# 08D-005.net
KiCad netlist of a schematic drawn in EAGLE
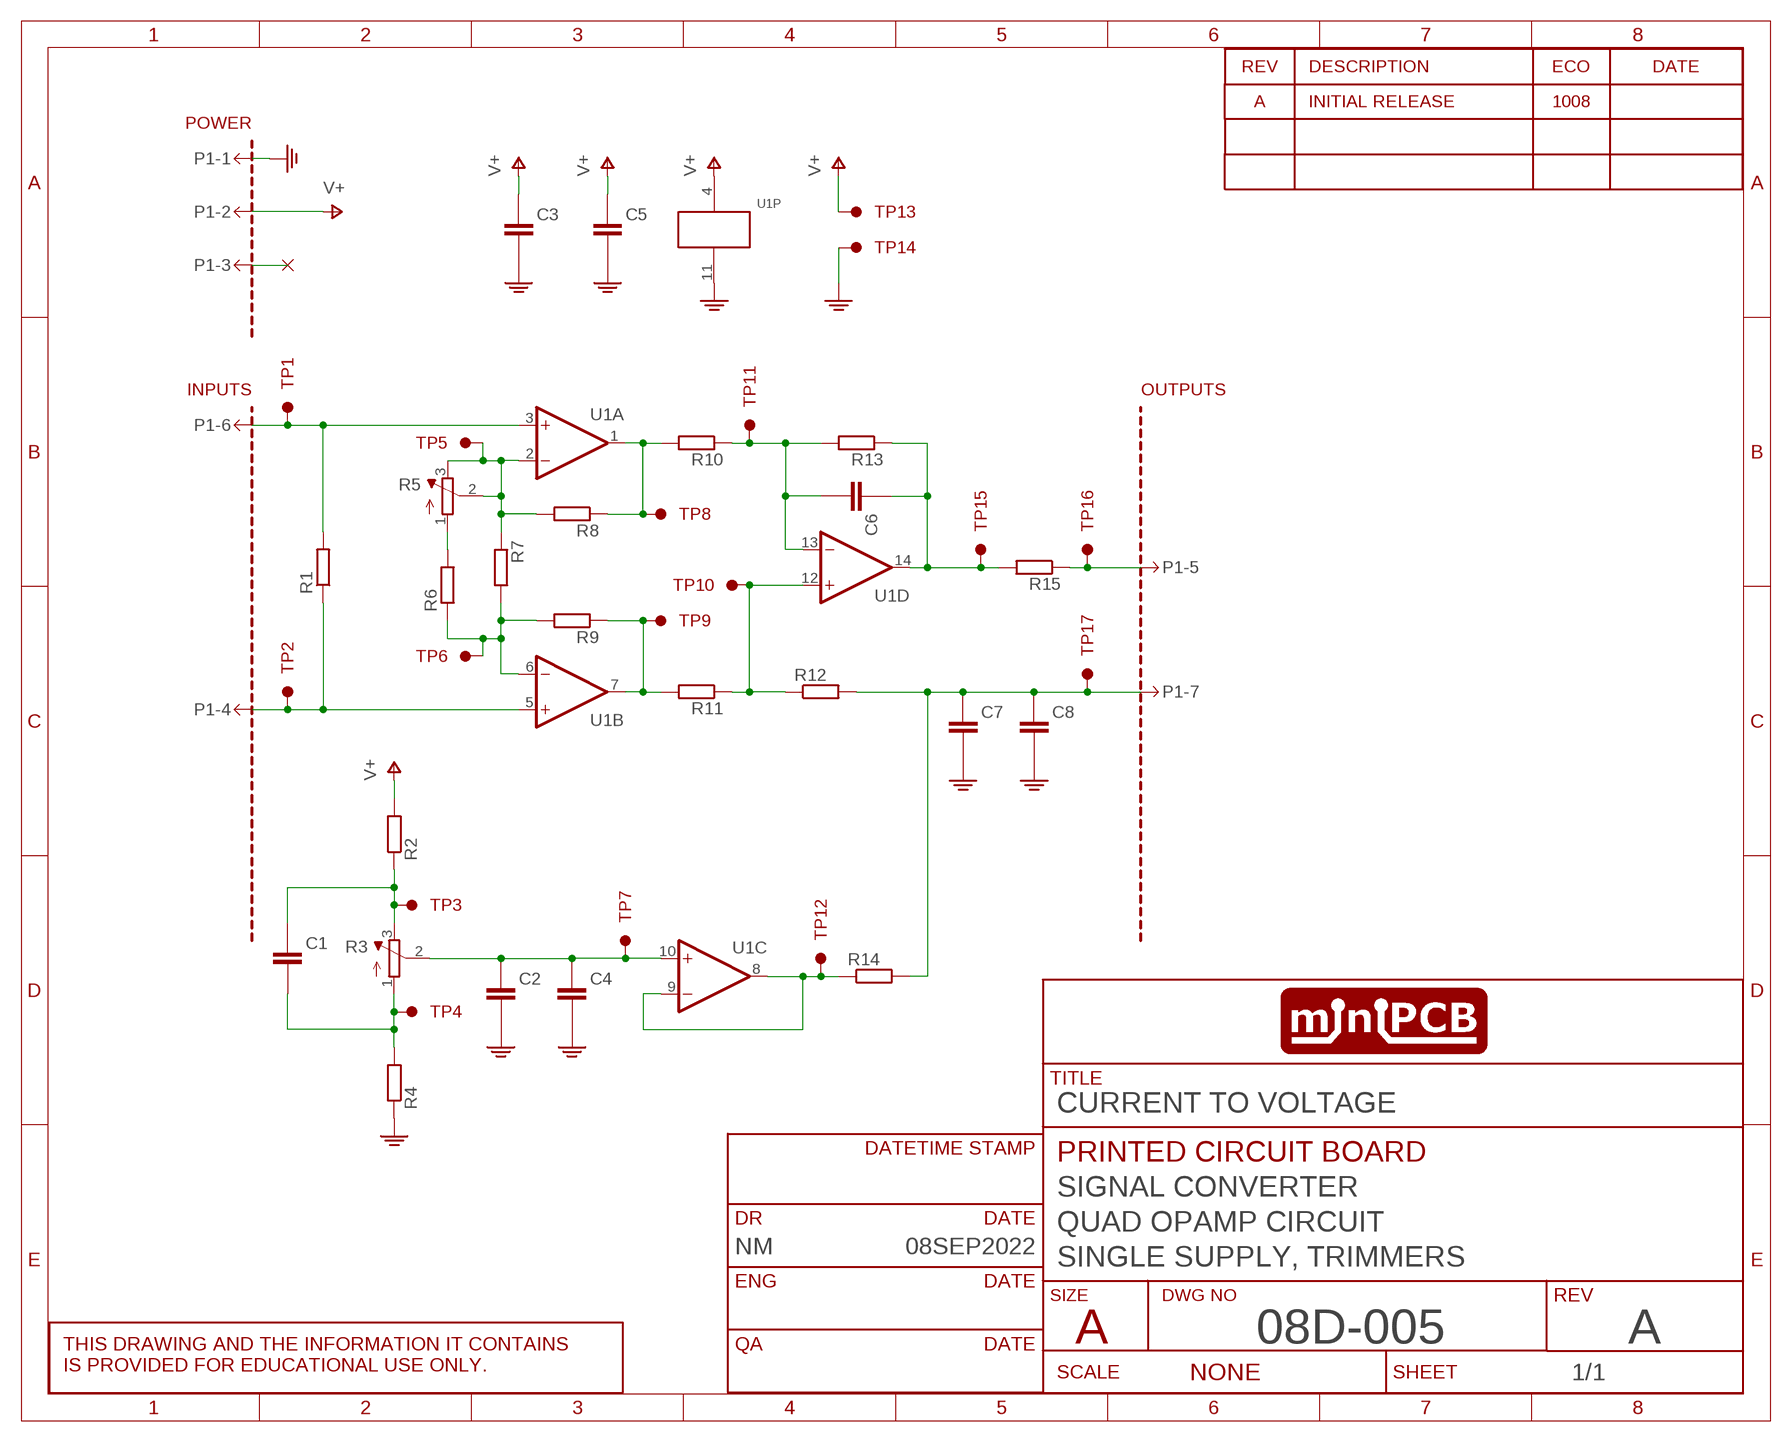
[diagram p0: schematic, sheet 1]

(export (version "E")
  (design (tool "Eeschema 10.0.6"))
  (components
    (comp (ref "C1")
      (value "CAPACITORTHD")
      (footprint "eagle-import:C050-024X044")
      (libsource (lib "eagle-import") (part "CAPACITORTHD"))
    )
    (comp (ref "C2")
      (value "CAPACITORTHD")
      (footprint "eagle-import:C050-024X044")
      (libsource (lib "eagle-import") (part "CAPACITORTHD"))
    )
    (comp (ref "C3")
      (value "CAPACITORTHD")
      (footprint "eagle-import:C050-024X044")
      (libsource (lib "eagle-import") (part "CAPACITORTHD"))
    )
    (comp (ref "C4")
      (value "CAPACITORTHD")
      (footprint "eagle-import:C050-024X044")
      (libsource (lib "eagle-import") (part "CAPACITORTHD"))
    )
    (comp (ref "C5")
      (value "CAPACITORTHD")
      (footprint "eagle-import:C050-024X044")
      (libsource (lib "eagle-import") (part "CAPACITORTHD"))
    )
    (comp (ref "C6")
      (value "CAPACITORTHD")
      (footprint "eagle-import:C050-024X044")
      (libsource (lib "eagle-import") (part "CAPACITORTHD"))
    )
    (comp (ref "C7")
      (value "CAPACITORTHD")
      (footprint "eagle-import:C050-024X044")
      (libsource (lib "eagle-import") (part "CAPACITORTHD"))
    )
    (comp (ref "C8")
      (value "CAPACITORTHD")
      (footprint "eagle-import:C050-024X044")
      (libsource (lib "eagle-import") (part "CAPACITORTHD"))
    )
    (comp (ref "P1-")
      (value "MINIPCB_7P50X100")
      (footprint "eagle-import:MINIPCB_7P_50X100")
      (fields (field (name "PART_NUMBER") "X08D-005-A"))
      (libsource (lib "eagle-import") (part "MINIPCB_7P50X100"))
    )
    (comp (ref "R1")
      (value "RESISTOR10MM")
      (footprint "eagle-import:0207_10")
      (libsource (lib "eagle-import") (part "RESISTOR10MM"))
    )
    (comp (ref "R2")
      (value "RESISTOR10MM")
      (footprint "eagle-import:0207_10")
      (libsource (lib "eagle-import") (part "RESISTOR10MM"))
    )
    (comp (ref "R3")
      (value "TRIMPOT0.100THD")
      (footprint "eagle-import:TRIM_0100")
      (libsource (lib "eagle-import") (part "TRIMPOT0.100THD"))
    )
    (comp (ref "R4")
      (value "RESISTOR10MM")
      (footprint "eagle-import:0207_10")
      (libsource (lib "eagle-import") (part "RESISTOR10MM"))
    )
    (comp (ref "R5")
      (value "TRIMPOT0.100THD")
      (footprint "eagle-import:TRIM_0100")
      (libsource (lib "eagle-import") (part "TRIMPOT0.100THD"))
    )
    (comp (ref "R6")
      (value "RESISTOR10MM")
      (footprint "eagle-import:0207_10")
      (libsource (lib "eagle-import") (part "RESISTOR10MM"))
    )
    (comp (ref "R7")
      (value "RESISTOR10MM")
      (footprint "eagle-import:0207_10")
      (libsource (lib "eagle-import") (part "RESISTOR10MM"))
    )
    (comp (ref "R8")
      (value "RESISTOR10MM")
      (footprint "eagle-import:0207_10")
      (libsource (lib "eagle-import") (part "RESISTOR10MM"))
    )
    (comp (ref "R9")
      (value "RESISTOR10MM")
      (footprint "eagle-import:0207_10")
      (libsource (lib "eagle-import") (part "RESISTOR10MM"))
    )
    (comp (ref "R10")
      (value "RESISTOR10MM")
      (footprint "eagle-import:0207_10")
      (libsource (lib "eagle-import") (part "RESISTOR10MM"))
    )
    (comp (ref "R11")
      (value "RESISTOR10MM")
      (footprint "eagle-import:0207_10")
      (libsource (lib "eagle-import") (part "RESISTOR10MM"))
    )
    (comp (ref "R12")
      (value "RESISTOR10MM")
      (footprint "eagle-import:0207_10")
      (libsource (lib "eagle-import") (part "RESISTOR10MM"))
    )
    (comp (ref "R13")
      (value "RESISTOR10MM")
      (footprint "eagle-import:0207_10")
      (libsource (lib "eagle-import") (part "RESISTOR10MM"))
    )
    (comp (ref "R14")
      (value "RESISTOR10MM")
      (footprint "eagle-import:0207_10")
      (libsource (lib "eagle-import") (part "RESISTOR10MM"))
    )
    (comp (ref "R15")
      (value "RESISTOR10MM")
      (footprint "eagle-import:0207_10")
      (libsource (lib "eagle-import") (part "RESISTOR10MM"))
    )
    (comp (ref "TP1")
      (value "TESTPOINTKE5000-SMTEXT")
      (footprint "eagle-import:PINS_1_TESTPOINT_KE5000_NOTEXT")
      (libsource (lib "eagle-import") (part "TESTPOINTKE5000-SMTEXT"))
    )
    (comp (ref "TP2")
      (value "TESTPOINTKE5000-SMTEXT")
      (footprint "eagle-import:PINS_1_TESTPOINT_KE5000_NOTEXT")
      (libsource (lib "eagle-import") (part "TESTPOINTKE5000-SMTEXT"))
    )
    (comp (ref "TP3")
      (value "TESTPOINTKE5000-SMTEXT")
      (footprint "eagle-import:PINS_1_TESTPOINT_KE5000_NOTEXT")
      (libsource (lib "eagle-import") (part "TESTPOINTKE5000-SMTEXT"))
    )
    (comp (ref "TP4")
      (value "TESTPOINTKE5000-SMTEXT")
      (footprint "eagle-import:PINS_1_TESTPOINT_KE5000_NOTEXT")
      (libsource (lib "eagle-import") (part "TESTPOINTKE5000-SMTEXT"))
    )
    (comp (ref "TP5")
      (value "TESTPOINTKE5000-SMTEXT")
      (footprint "eagle-import:PINS_1_TESTPOINT_KE5000_NOTEXT")
      (libsource (lib "eagle-import") (part "TESTPOINTKE5000-SMTEXT"))
    )
    (comp (ref "TP6")
      (value "TESTPOINTKE5000-SMTEXT")
      (footprint "eagle-import:PINS_1_TESTPOINT_KE5000_NOTEXT")
      (libsource (lib "eagle-import") (part "TESTPOINTKE5000-SMTEXT"))
    )
    (comp (ref "TP7")
      (value "TESTPOINTKE5000-SMTEXT")
      (footprint "eagle-import:PINS_1_TESTPOINT_KE5000_NOTEXT")
      (libsource (lib "eagle-import") (part "TESTPOINTKE5000-SMTEXT"))
    )
    (comp (ref "TP8")
      (value "TESTPOINTKE5000-SMTEXT")
      (footprint "eagle-import:PINS_1_TESTPOINT_KE5000_NOTEXT")
      (libsource (lib "eagle-import") (part "TESTPOINTKE5000-SMTEXT"))
    )
    (comp (ref "TP9")
      (value "TESTPOINTKE5000-SMTEXT")
      (footprint "eagle-import:PINS_1_TESTPOINT_KE5000_NOTEXT")
      (libsource (lib "eagle-import") (part "TESTPOINTKE5000-SMTEXT"))
    )
    (comp (ref "TP10")
      (value "TESTPOINTKE5000-SMTEXT")
      (footprint "eagle-import:PINS_1_TESTPOINT_KE5000_NOTEXT")
      (libsource (lib "eagle-import") (part "TESTPOINTKE5000-SMTEXT"))
    )
    (comp (ref "TP11")
      (value "TESTPOINTKE5000-SMTEXT")
      (footprint "eagle-import:PINS_1_TESTPOINT_KE5000_NOTEXT")
      (libsource (lib "eagle-import") (part "TESTPOINTKE5000-SMTEXT"))
    )
    (comp (ref "TP12")
      (value "TESTPOINTKE5000-SMTEXT")
      (footprint "eagle-import:PINS_1_TESTPOINT_KE5000_NOTEXT")
      (libsource (lib "eagle-import") (part "TESTPOINTKE5000-SMTEXT"))
    )
    (comp (ref "TP13")
      (value "TESTPOINTKE5000-SMTEXT")
      (footprint "eagle-import:PINS_1_TESTPOINT_KE5000_NOTEXT")
      (libsource (lib "eagle-import") (part "TESTPOINTKE5000-SMTEXT"))
    )
    (comp (ref "TP14")
      (value "TESTPOINTKE5000-SMTEXT")
      (footprint "eagle-import:PINS_1_TESTPOINT_KE5000_NOTEXT")
      (libsource (lib "eagle-import") (part "TESTPOINTKE5000-SMTEXT"))
    )
    (comp (ref "TP15")
      (value "TESTPOINTKE5000-SMTEXT")
      (footprint "eagle-import:PINS_1_TESTPOINT_KE5000_NOTEXT")
      (libsource (lib "eagle-import") (part "TESTPOINTKE5000-SMTEXT"))
    )
    (comp (ref "TP16")
      (value "TESTPOINTKE5000-SMTEXT")
      (footprint "eagle-import:PINS_1_TESTPOINT_KE5000_NOTEXT")
      (libsource (lib "eagle-import") (part "TESTPOINTKE5000-SMTEXT"))
    )
    (comp (ref "TP17")
      (value "TESTPOINTKE5000-SMTEXT")
      (footprint "eagle-import:PINS_1_TESTPOINT_KE5000_NOTEXT")
      (libsource (lib "eagle-import") (part "TESTPOINTKE5000-SMTEXT"))
    )
    (comp (ref "U1")
      (value "OPAMP_QUADTHD")
      (footprint "eagle-import:DIL14")
      (libsource (lib "eagle-import") (part "OPAMP_QUADTHD"))
    )
  )
  (nets
    (net (code "1") (name "GND") (class "Default")
      (node (ref "C2") (pin "2") (pinfunction "-_2") (pintype "passive"))
      (node (ref "C3") (pin "2") (pinfunction "-_2") (pintype "passive"))
      (node (ref "C4") (pin "2") (pinfunction "-_2") (pintype "passive"))
      (node (ref "C5") (pin "2") (pinfunction "-_2") (pintype "passive"))
      (node (ref "C7") (pin "2") (pinfunction "-_2") (pintype "passive"))
      (node (ref "C8") (pin "2") (pinfunction "-_2") (pintype "passive"))
      (node (ref "P1-") (pin "1") (pinfunction "1_1") (pintype "bidirectional"))
      (node (ref "R4") (pin "1") (pinfunction "1_1") (pintype "passive"))
      (node (ref "TP14") (pin "1") (pinfunction "1_1") (pintype "bidirectional"))
      (node (ref "U1") (pin "11") (pinfunction "V-_11") (pintype "power_in"))
    )
    (net (code "2") (name "Net-(C1-+)") (class "Default")
      (node (ref "C1") (pin "1") (pinfunction "+_1") (pintype "passive"))
      (node (ref "R2") (pin "1") (pinfunction "1_1") (pintype "passive"))
      (node (ref "R3") (pin "3") (pinfunction "E_3") (pintype "passive"))
      (node (ref "TP3") (pin "1") (pinfunction "1_1") (pintype "bidirectional"))
    )
    (net (code "3") (name "Net-(C1--)") (class "Default")
      (node (ref "C1") (pin "2") (pinfunction "-_2") (pintype "passive"))
      (node (ref "R3") (pin "1") (pinfunction "A_1") (pintype "passive"))
      (node (ref "R4") (pin "2") (pinfunction "2_2") (pintype "passive"))
      (node (ref "TP4") (pin "1") (pinfunction "1_1") (pintype "bidirectional"))
    )
    (net (code "4") (name "Net-(C2-+)") (class "Default")
      (node (ref "C2") (pin "1") (pinfunction "+_1") (pintype "passive"))
      (node (ref "C4") (pin "1") (pinfunction "+_1") (pintype "passive"))
      (node (ref "R3") (pin "2") (pinfunction "S_2") (pintype "passive"))
      (node (ref "TP7") (pin "1") (pinfunction "1_1") (pintype "bidirectional"))
      (node (ref "U1") (pin "10") (pinfunction "+IN_10") (pintype "input"))
    )
    (net (code "5") (name "Net-(C6-+)") (class "Default")
      (node (ref "C6") (pin "1") (pinfunction "+_1") (pintype "passive"))
      (node (ref "R13") (pin "1") (pinfunction "1_1") (pintype "passive"))
      (node (ref "R15") (pin "2") (pinfunction "2_2") (pintype "passive"))
      (node (ref "TP15") (pin "1") (pinfunction "1_1") (pintype "bidirectional"))
      (node (ref "U1") (pin "14") (pinfunction "OUT_14") (pintype "output"))
    )
    (net (code "6") (name "Net-(C6--)") (class "Default")
      (node (ref "C6") (pin "2") (pinfunction "-_2") (pintype "passive"))
      (node (ref "R10") (pin "1") (pinfunction "1_1") (pintype "passive"))
      (node (ref "R13") (pin "2") (pinfunction "2_2") (pintype "passive"))
      (node (ref "TP11") (pin "1") (pinfunction "1_1") (pintype "bidirectional"))
      (node (ref "U1") (pin "13") (pinfunction "-IN_13") (pintype "input"))
    )
    (net (code "7") (name "Net-(C7-+)") (class "Default")
      (node (ref "C7") (pin "1") (pinfunction "+_1") (pintype "passive"))
      (node (ref "C8") (pin "1") (pinfunction "+_1") (pintype "passive"))
      (node (ref "P1-") (pin "7") (pinfunction "1_7") (pintype "bidirectional"))
      (node (ref "R12") (pin "2") (pinfunction "2_2") (pintype "passive"))
      (node (ref "R14") (pin "2") (pinfunction "2_2") (pintype "passive"))
      (node (ref "TP17") (pin "1") (pinfunction "1_1") (pintype "bidirectional"))
    )
    (net (code "8") (name "Net-(P1-D-1)") (class "Default")
      (node (ref "P1-") (pin "4") (pinfunction "1_4") (pintype "bidirectional"))
      (node (ref "R1") (pin "1") (pinfunction "1_1") (pintype "passive"))
      (node (ref "TP2") (pin "1") (pinfunction "1_1") (pintype "bidirectional"))
      (node (ref "U1") (pin "5") (pinfunction "+IN_5") (pintype "input"))
    )
    (net (code "9") (name "Net-(P1-E-1)") (class "Default")
      (node (ref "P1-") (pin "5") (pinfunction "1_5") (pintype "bidirectional"))
      (node (ref "R15") (pin "1") (pinfunction "1_1") (pintype "passive"))
      (node (ref "TP16") (pin "1") (pinfunction "1_1") (pintype "bidirectional"))
    )
    (net (code "10") (name "Net-(P1-F-1)") (class "Default")
      (node (ref "P1-") (pin "6") (pinfunction "1_6") (pintype "bidirectional"))
      (node (ref "R1") (pin "2") (pinfunction "2_2") (pintype "passive"))
      (node (ref "TP1") (pin "1") (pinfunction "1_1") (pintype "bidirectional"))
      (node (ref "U1") (pin "3") (pinfunction "+IN_3") (pintype "input"))
    )
    (net (code "11") (name "Net-(R5-A)") (class "Default")
      (node (ref "R5") (pin "1") (pinfunction "A_1") (pintype "passive"))
      (node (ref "R6") (pin "2") (pinfunction "2_2") (pintype "passive"))
    )
    (net (code "12") (name "Net-(R5-E)") (class "Default")
      (node (ref "R5") (pin "2") (pinfunction "S_2") (pintype "passive"))
      (node (ref "R5") (pin "3") (pinfunction "E_3") (pintype "passive"))
      (node (ref "R7") (pin "1") (pinfunction "1_1") (pintype "passive"))
      (node (ref "R8") (pin "2") (pinfunction "2_2") (pintype "passive"))
      (node (ref "TP5") (pin "1") (pinfunction "1_1") (pintype "bidirectional"))
      (node (ref "U1") (pin "2") (pinfunction "-IN_2") (pintype "input"))
    )
    (net (code "13") (name "Net-(U1A-OUT)") (class "Default")
      (node (ref "R10") (pin "2") (pinfunction "2_2") (pintype "passive"))
      (node (ref "R8") (pin "1") (pinfunction "1_1") (pintype "passive"))
      (node (ref "TP8") (pin "1") (pinfunction "1_1") (pintype "bidirectional"))
      (node (ref "U1") (pin "1") (pinfunction "OUT_1") (pintype "output"))
    )
    (net (code "14") (name "Net-(U1B--IN)") (class "Default")
      (node (ref "R6") (pin "1") (pinfunction "1_1") (pintype "passive"))
      (node (ref "R7") (pin "2") (pinfunction "2_2") (pintype "passive"))
      (node (ref "R9") (pin "2") (pinfunction "2_2") (pintype "passive"))
      (node (ref "TP6") (pin "1") (pinfunction "1_1") (pintype "bidirectional"))
      (node (ref "U1") (pin "6") (pinfunction "-IN_6") (pintype "input"))
    )
    (net (code "15") (name "Net-(U1B-OUT)") (class "Default")
      (node (ref "R11") (pin "2") (pinfunction "2_2") (pintype "passive"))
      (node (ref "R9") (pin "1") (pinfunction "1_1") (pintype "passive"))
      (node (ref "TP9") (pin "1") (pinfunction "1_1") (pintype "bidirectional"))
      (node (ref "U1") (pin "7") (pinfunction "OUT_7") (pintype "output"))
    )
    (net (code "16") (name "Net-(U1C--IN)") (class "Default")
      (node (ref "R14") (pin "1") (pinfunction "1_1") (pintype "passive"))
      (node (ref "TP12") (pin "1") (pinfunction "1_1") (pintype "bidirectional"))
      (node (ref "U1") (pin "8") (pinfunction "OUT_8") (pintype "output"))
      (node (ref "U1") (pin "9") (pinfunction "-IN_9") (pintype "input"))
    )
    (net (code "17") (name "Net-(U1D-+IN)") (class "Default")
      (node (ref "R11") (pin "1") (pinfunction "1_1") (pintype "passive"))
      (node (ref "R12") (pin "1") (pinfunction "1_1") (pintype "passive"))
      (node (ref "TP10") (pin "1") (pinfunction "1_1") (pintype "bidirectional"))
      (node (ref "U1") (pin "12") (pinfunction "+IN_12") (pintype "input"))
    )
    (net (code "18") (name "V+") (class "Default")
      (node (ref "C3") (pin "1") (pinfunction "+_1") (pintype "passive"))
      (node (ref "C5") (pin "1") (pinfunction "+_1") (pintype "passive"))
      (node (ref "P1-") (pin "2") (pinfunction "1_2") (pintype "bidirectional"))
      (node (ref "R2") (pin "2") (pinfunction "2_2") (pintype "passive"))
      (node (ref "TP13") (pin "1") (pinfunction "1_1") (pintype "bidirectional"))
      (node (ref "U1") (pin "4") (pinfunction "V+_4") (pintype "power_in"))
    )
    (net (code "19") (name "unconnected-(P1-C-1-Pad3)") (class "Default")
      (node (ref "P1-") (pin "3") (pinfunction "1_3") (pintype "bidirectional"))
    )
  )
)
